# schematic.net
KiCad netlist of a schematic drawn in EAGLE
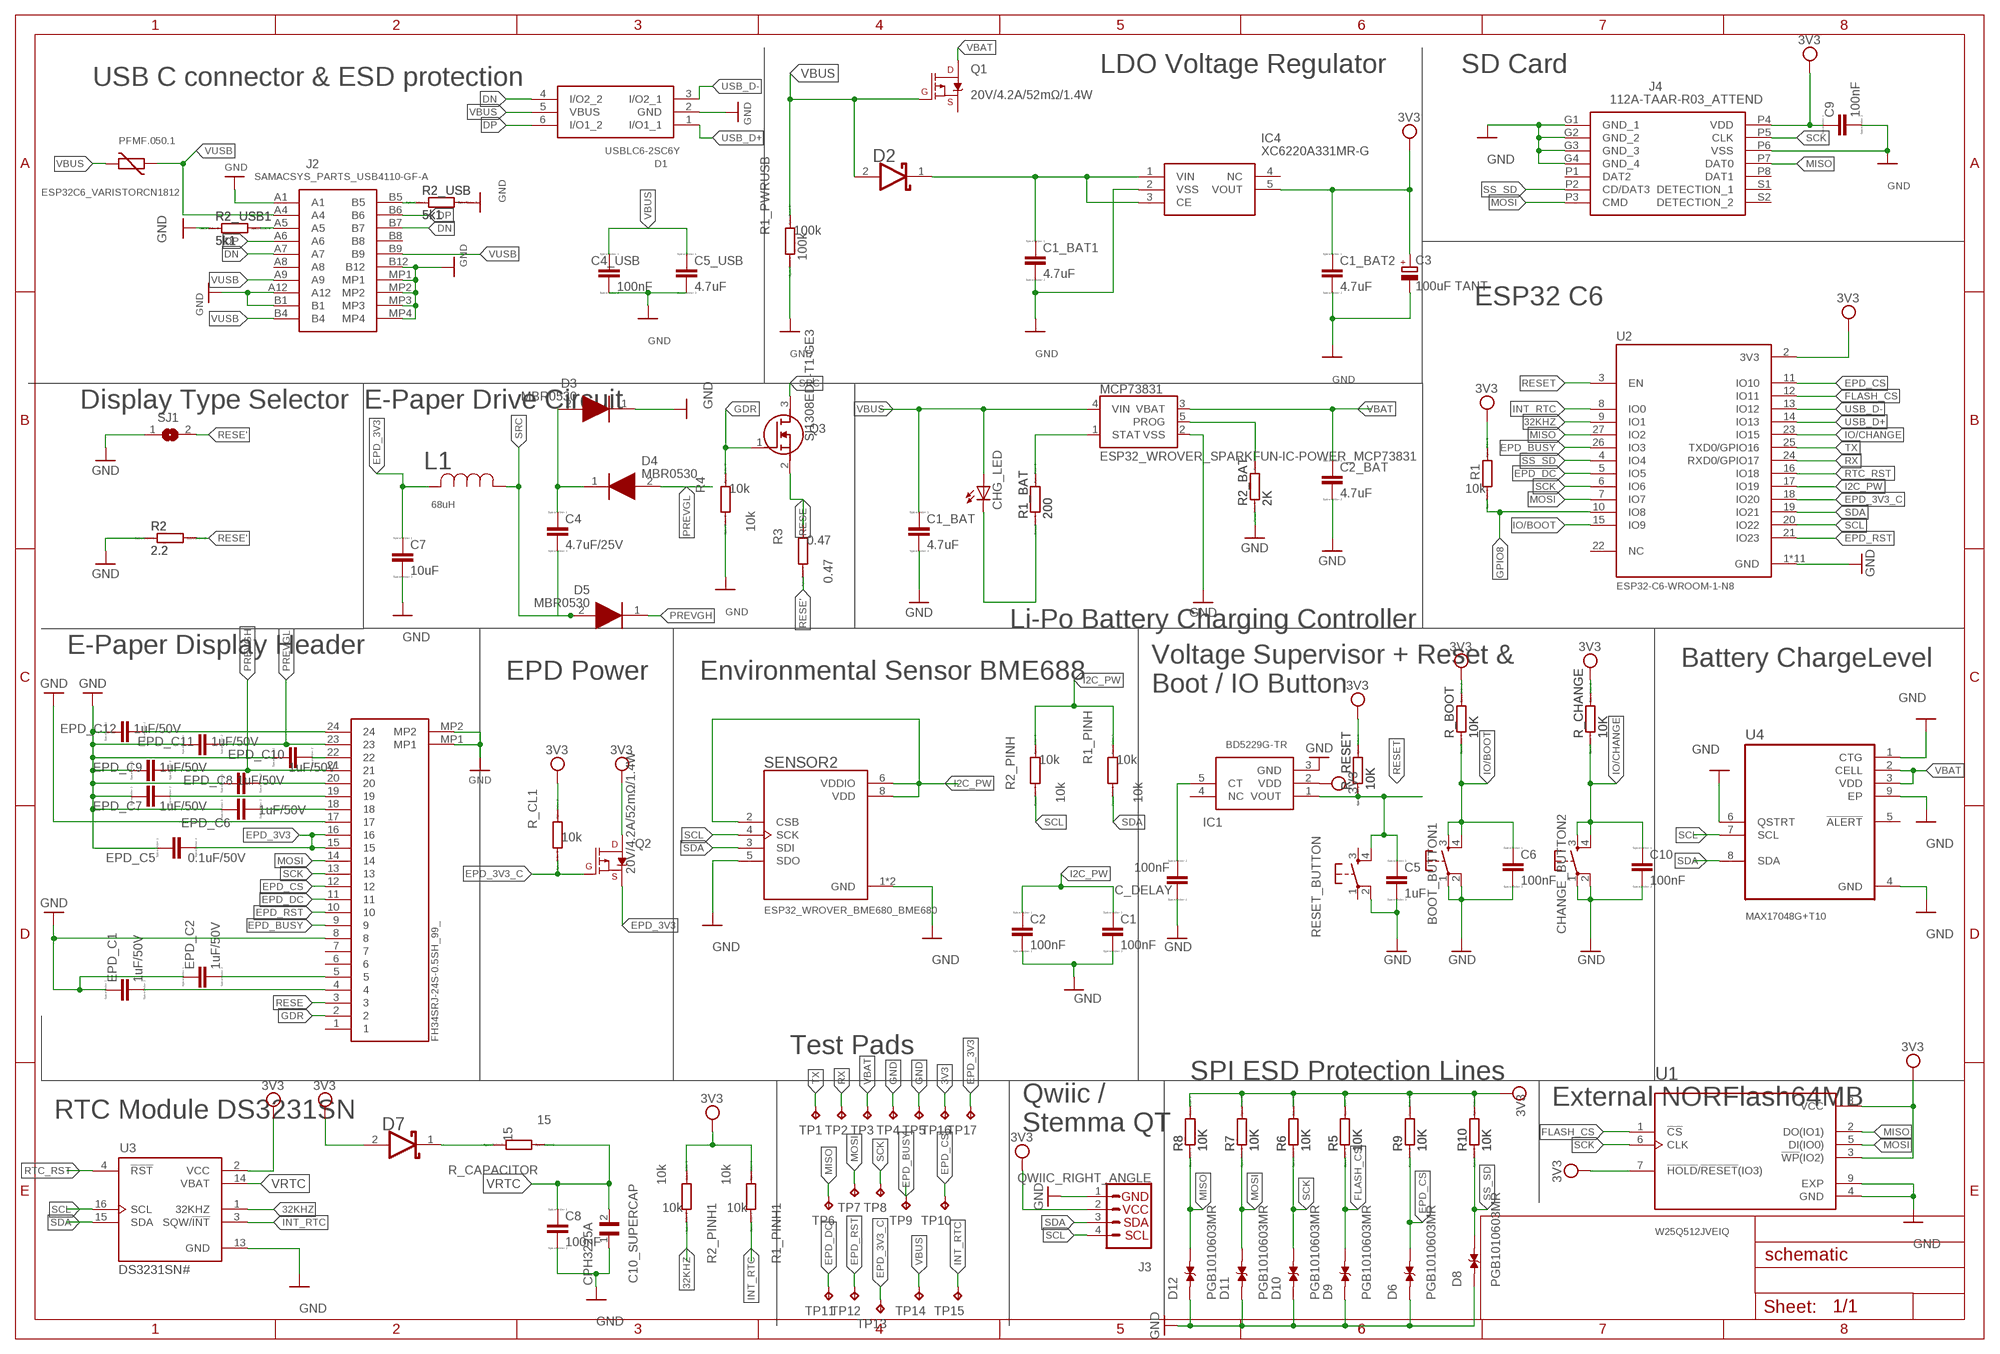
[diagram p0: schematic, sheet 1]

(export (version "E")
  (design (tool "Eeschema 10.0.6"))
  (components
    (comp (ref "BOOT_BUTTON1")
      (value "BUTTON_CUSYOMV1")
      (footprint "eagle-import:MYBUTTON")
      (libsource (lib "eagle-import") (part "BUTTON_CUSYOMV1"))
    )
    (comp (ref "C1")
      (value "100nF")
      (footprint "eagle-import:EAGLE-LTSPICE_C0402")
      (libsource (lib "eagle-import") (part "DeskAssistant v19 v1_vf.nBZE1evWTd-OCEZQXOw4Cw_EAGLE-LTSPICE_CC0402"))
    )
    (comp (ref "C1_BAT")
      (value "4.7uF")
      (footprint "eagle-import:EAGLE-LTSPICE_C0402")
      (libsource (lib "eagle-import") (part "EAGLE-LTSPICE_CC0402"))
    )
    (comp (ref "C1_BAT1")
      (value "4.7uF")
      (footprint "eagle-import:EAGLE-LTSPICE_C0402")
      (libsource (lib "eagle-import") (part "DeskAssistant v19 v1_vf.nBZE1evWTd-OCEZQXOw4Cw_EAGLE-LTSPICE_CC0402"))
    )
    (comp (ref "C1_BAT2")
      (value "4.7uF")
      (footprint "eagle-import:EAGLE-LTSPICE_C0402")
      (libsource (lib "eagle-import") (part "DeskAssistant v19 v1_vf.nBZE1evWTd-OCEZQXOw4Cw_EAGLE-LTSPICE_CC0402"))
    )
    (comp (ref "C2")
      (value "100nF")
      (footprint "eagle-import:EAGLE-LTSPICE_C0402")
      (libsource (lib "eagle-import") (part "DeskAssistant v19 v1_vf.nBZE1evWTd-OCEZQXOw4Cw_EAGLE-LTSPICE_CC0402"))
    )
    (comp (ref "C2_BAT")
      (value "4.7uF")
      (footprint "eagle-import:EAGLE-LTSPICE_C0402")
      (libsource (lib "eagle-import") (part "EAGLE-LTSPICE_CC0402"))
    )
    (comp (ref "C3")
      (value "100uF TANT")
      (footprint "eagle-import:RCL_CT3528")
      (libsource (lib "eagle-import") (part "RCL_CPOL-EUCT3528"))
    )
    (comp (ref "C4")
      (value "4.7uF/25V")
      (footprint "eagle-import:EAGLE-LTSPICE_C0402")
      (libsource (lib "eagle-import") (part "DeskAssistant v19 v1_vf.nBZE1evWTd-OCEZQXOw4Cw_EAGLE-LTSPICE_CC0402"))
    )
    (comp (ref "C4_USB")
      (value "100nF")
      (footprint "eagle-import:EAGLE-LTSPICE_C0402")
      (libsource (lib "eagle-import") (part "DeskAssistant v19 v1_vf.nBZE1evWTd-OCEZQXOw4Cw_EAGLE-LTSPICE_CC0402"))
    )
    (comp (ref "C5")
      (value "1uF")
      (footprint "eagle-import:EAGLE-LTSPICE_C0402")
      (libsource (lib "eagle-import") (part "EAGLE-LTSPICE_CC0402"))
    )
    (comp (ref "C5_USB")
      (value "4.7uF")
      (footprint "eagle-import:EAGLE-LTSPICE_C0402")
      (libsource (lib "eagle-import") (part "DeskAssistant v19 v1_vf.nBZE1evWTd-OCEZQXOw4Cw_EAGLE-LTSPICE_CC0402"))
    )
    (comp (ref "C6")
      (value "100nF")
      (footprint "eagle-import:EAGLE-LTSPICE_C0402")
      (libsource (lib "eagle-import") (part "EAGLE-LTSPICE_CC0402"))
    )
    (comp (ref "C7")
      (value "10uF")
      (footprint "eagle-import:EAGLE-LTSPICE_C0402")
      (libsource (lib "eagle-import") (part "DeskAssistant v19 v1_vf.nBZE1evWTd-OCEZQXOw4Cw_EAGLE-LTSPICE_CC0402"))
    )
    (comp (ref "C8")
      (value "100nF")
      (footprint "eagle-import:EAGLE-LTSPICE_C0402")
      (libsource (lib "eagle-import") (part "DeskAssistant v19 v1_vf.nBZE1evWTd-OCEZQXOw4Cw_EAGLE-LTSPICE_CC0402"))
    )
    (comp (ref "C9")
      (value "100nF")
      (footprint "eagle-import:EAGLE-LTSPICE_C0402")
      (libsource (lib "eagle-import") (part "DeskAssistant v19 v1_vf.nBZE1evWTd-OCEZQXOw4Cw_EAGLE-LTSPICE_CC0402"))
    )
    (comp (ref "C10")
      (value "100nF")
      (footprint "eagle-import:EAGLE-LTSPICE_C0402")
      (libsource (lib "eagle-import") (part "EAGLE-LTSPICE_CC0402"))
    )
    (comp (ref "C10_SUPERCAP")
      (value "CPH3225A")
      (footprint "eagle-import:CAPCP3225X100N")
      (fields (field (name "MF") "Seiko Instruments"))
      (libsource (lib "eagle-import") (part "CPH3225A"))
    )
    (comp (ref "CHANGE_BUTTON2")
      (value "BUTTON_CUSYOMV1")
      (footprint "eagle-import:MYBUTTON")
      (libsource (lib "eagle-import") (part "BUTTON_CUSYOMV1"))
    )
    (comp (ref "CHG_LED")
      (value "ADAFRUIT_LEDCHIP-LED0603")
      (footprint "eagle-import:ADAFRUIT_CHIP-LED0603")
      (libsource (lib "eagle-import") (part "ADAFRUIT_LEDCHIP-LED0603"))
    )
    (comp (ref "C_DELAY")
      (value "100nF")
      (footprint "eagle-import:EAGLE-LTSPICE_C0402")
      (libsource (lib "eagle-import") (part "EAGLE-LTSPICE_CC0402"))
    )
    (comp (ref "D1")
      (value "USBLC6-2SC6Y")
      (footprint "eagle-import:SOT95P280X145-6N")
      (fields (field (name "MF") "STMicroelectronics"))
      (libsource (lib "eagle-import") (part "USBLC6-2SC6Y"))
    )
    (comp (ref "D2")
      (value "ESP32_WROVER_AVX---SD0805S020S1R0_AVX_SD0805S020S1R0_0_0AVX_SD0805S020S1R0_0_0")
      (footprint "eagle-import:ESP32_WROVER_AVX---SD0805S020S1R0_AVX_SD0805S020S1R0_0")
      (fields
        (field (name "DIGIKEY_PART_NUMBER") "478-7800-1-ND")
        (field (name "MF") "AVX")
        (field (name "MOUSER_PART_NUMBER") "581-SD0805S020S1R0")
      )
      (libsource (lib "eagle-import") (part "ESP32_WROVER_AVX---SD0805S020S1R0_AVX_SD0805S020S1R0_0_0AVX_SD0805S020S1R0_0_0"))
    )
    (comp (ref "D3")
      (value "MBR0530")
      (footprint "eagle-import:SOD3716X135N")
      (fields (field (name "MF") "ON Semiconductor"))
      (libsource (lib "eagle-import") (part "MBR0530"))
    )
    (comp (ref "D4")
      (value "MBR0530")
      (footprint "eagle-import:SOD3716X135N")
      (fields (field (name "MF") "ON Semiconductor"))
      (libsource (lib "eagle-import") (part "MBR0530"))
    )
    (comp (ref "D5")
      (value "MBR0530")
      (footprint "eagle-import:SOD3716X135N")
      (fields (field (name "MF") "ON Semiconductor"))
      (libsource (lib "eagle-import") (part "MBR0530"))
    )
    (comp (ref "D6")
      (value "PGB1010603MR")
      (footprint "eagle-import:DIOC1608X36N")
      (fields (field (name "MF") "Littelfuse Inc."))
      (libsource (lib "eagle-import") (part "PGB1010603MR"))
    )
    (comp (ref "D7")
      (value "ESP32_WROVER_AVX---SD0805S020S1R0_AVX_SD0805S020S1R0_0_0AVX_SD0805S020S1R0_0_0")
      (footprint "eagle-import:ESP32_WROVER_AVX---SD0805S020S1R0_AVX_SD0805S020S1R0_0")
      (fields
        (field (name "DIGIKEY_PART_NUMBER") "478-7800-1-ND")
        (field (name "MF") "AVX")
        (field (name "MOUSER_PART_NUMBER") "581-SD0805S020S1R0")
      )
      (libsource (lib "eagle-import") (part "ESP32_WROVER_AVX---SD0805S020S1R0_AVX_SD0805S020S1R0_0_0AVX_SD0805S020S1R0_0_0"))
    )
    (comp (ref "D8")
      (value "PGB1010603MR")
      (footprint "eagle-import:DIOC1608X36N")
      (fields (field (name "MF") "Littelfuse Inc."))
      (libsource (lib "eagle-import") (part "PGB1010603MR"))
    )
    (comp (ref "D9")
      (value "PGB1010603MR")
      (footprint "eagle-import:DIOC1608X36N")
      (fields (field (name "MF") "Littelfuse Inc."))
      (libsource (lib "eagle-import") (part "PGB1010603MR"))
    )
    (comp (ref "D10")
      (value "PGB1010603MR")
      (footprint "eagle-import:DIOC1608X36N")
      (fields (field (name "MF") "Littelfuse Inc."))
      (libsource (lib "eagle-import") (part "PGB1010603MR"))
    )
    (comp (ref "D11")
      (value "PGB1010603MR")
      (footprint "eagle-import:DIOC1608X36N")
      (fields (field (name "MF") "Littelfuse Inc."))
      (libsource (lib "eagle-import") (part "PGB1010603MR"))
    )
    (comp (ref "D12")
      (value "PGB1010603MR")
      (footprint "eagle-import:DIOC1608X36N")
      (fields (field (name "MF") "Littelfuse Inc."))
      (libsource (lib "eagle-import") (part "PGB1010603MR"))
    )
    (comp (ref "EPD_C1")
      (value "1uF/50V")
      (footprint "eagle-import:EAGLE-LTSPICE_C0402")
      (libsource (lib "eagle-import") (part "EAGLE-LTSPICE_CC0402"))
    )
    (comp (ref "EPD_C2")
      (value "1uF/50V")
      (footprint "eagle-import:EAGLE-LTSPICE_C0402")
      (libsource (lib "eagle-import") (part "EAGLE-LTSPICE_CC0402"))
    )
    (comp (ref "EPD_C5")
      (value "0.1uF/50V")
      (footprint "eagle-import:EAGLE-LTSPICE_C0402")
      (libsource (lib "eagle-import") (part "EAGLE-LTSPICE_CC0402"))
    )
    (comp (ref "EPD_C6")
      (value "1uF/50V")
      (footprint "eagle-import:EAGLE-LTSPICE_C0402")
      (libsource (lib "eagle-import") (part "EAGLE-LTSPICE_CC0402"))
    )
    (comp (ref "EPD_C7")
      (value "1uF/50V")
      (footprint "eagle-import:EAGLE-LTSPICE_C0402")
      (libsource (lib "eagle-import") (part "EAGLE-LTSPICE_CC0402"))
    )
    (comp (ref "EPD_C8")
      (value "1uF/50V")
      (footprint "eagle-import:EAGLE-LTSPICE_C0402")
      (libsource (lib "eagle-import") (part "EAGLE-LTSPICE_CC0402"))
    )
    (comp (ref "EPD_C9")
      (value "1uF/50V")
      (footprint "eagle-import:EAGLE-LTSPICE_C0402")
      (libsource (lib "eagle-import") (part "EAGLE-LTSPICE_CC0402"))
    )
    (comp (ref "EPD_C10")
      (value "1uF/50V")
      (footprint "eagle-import:EAGLE-LTSPICE_C0402")
      (libsource (lib "eagle-import") (part "EAGLE-LTSPICE_CC0402"))
    )
    (comp (ref "EPD_C11")
      (value "1uF/50V")
      (footprint "eagle-import:EAGLE-LTSPICE_C0402")
      (libsource (lib "eagle-import") (part "EAGLE-LTSPICE_CC0402"))
    )
    (comp (ref "EPD_C12")
      (value "1uF/50V")
      (footprint "eagle-import:EAGLE-LTSPICE_C0402")
      (libsource (lib "eagle-import") (part "EAGLE-LTSPICE_CC0402"))
    )
    (comp (ref "FH34SRJ-24S-0.5SH_99_")
      (value "FH34SRJ-24S-0.5SH_99_")
      (footprint "eagle-import:FH34SRJ24S05SH99")
      (fields
        (field (name "MANUFACTURER_PART_NUMBER") "FH34SRJ-24S-0.5SH(99)")
        (field (name "MOUSER_PART_NUMBER") "798-FH34SRJ24S05SH99")
      )
      (libsource (lib "eagle-import") (part "FH34SRJ-24S-0.5SH_99_"))
    )
    (comp (ref "IC1")
      (value "BD5229G-TR")
      (footprint "eagle-import:SOT95P280X125-5N")
      (fields (field (name "MOUSER_PART_NUMBER") "755-BD5229G-TR"))
      (libsource (lib "eagle-import") (part "BD5229G-TR"))
    )
    (comp (ref "IC4")
      (value "XC6220A331MR-G")
      (footprint "eagle-import:SOT95P280X120-5N")
      (fields (field (name "MOUSER_PART_NUMBER") "865-XC6220A331MR-G"))
      (libsource (lib "eagle-import") (part "XC6220A331MR-G"))
    )
    (comp (ref "J2")
      (value "SAMACSYS_PARTS_USB4110-GF-A")
      (footprint "eagle-import:SAMACSYS_PARTS_USB4110GFA")
      (fields
        (field (name "MANUFACTURER_PART_NUMBER") "USB4110-GF-A")
        (field (name "MOUSER_PART_NUMBER") "640-USB4110-GF-A")
      )
      (libsource (lib "eagle-import") (part "SAMACSYS_PARTS_USB4110-GF-A"))
    )
    (comp (ref "J3")
      (value "QWIIC_RIGHT_ANGLE")
      (footprint "eagle-import:JST04_1MM_RA")
      (libsource (lib "eagle-import") (part "QWIIC_CONNECTORJS-1MM"))
    )
    (comp (ref "J4")
      (value "112A-TAAR-R03_ATTEND")
      (footprint "eagle-import:112ATAARR03ATTEND")
      (fields (field (name "MANUFACTURER_PART_NUMBER") "112A-TAAR-R03 ATTEND"))
      (libsource (lib "eagle-import") (part "112A-TAAR-R03_ATTEND"))
    )
    (comp (ref "L1")
      (value "68uH")
      (footprint "eagle-import:IND_4828-WE-TPC_WRE")
      (fields
        (field (name "MANUFACTURER_PART_NUMBER") "744043680")
        (field (name "COPYRIGHT") "Copyright (C) 2024 Ultra Librarian. All rights reserved.")
      )
      (libsource (lib "eagle-import") (part "744043680IND_4828-WE-TPC_WRE"))
    )
    (comp (ref "MCP73831")
      (value "ESP32_WROVER_SPARKFUN-IC-POWER_MCP73831")
      (footprint "eagle-import:ESP32_WROVER_SPARKFUN-IC-POWER_SOT23-5")
      (libsource (lib "eagle-import") (part "ESP32_WROVER_SPARKFUN-IC-POWER_MCP73831"))
    )
    (comp (ref "PFMF.050.1")
      (value "ESP32C6_VARISTORCN1812")
      (footprint "eagle-import:ESP32C6_VARISTOR_CT_CN1812")
      (libsource (lib "eagle-import") (part "ESP32C6_VARISTORCN1812"))
    )
    (comp (ref "Q1")
      (value "20V/4.2A/52mΩ/1.4W")
      (footprint "eagle-import:ESP32_WROVER_SPARKFUN-DISCRETESEMI_SOT23-3")
      (libsource (lib "eagle-import") (part "ESP32_WROVER_SPARKFUN-DISCRETESEMI_MOSFET_PCH-DMG2305UX-7"))
    )
    (comp (ref "Q2")
      (value "20V/4.2A/52mΩ/1.4W")
      (footprint "eagle-import:ESP32_WROVER_SPARKFUN-DISCRETESEMI_SOT23-3")
      (libsource (lib "eagle-import") (part "ESP32_WROVER_SPARKFUN-DISCRETESEMI_MOSFET_PCH-DMG2305UX-7"))
    )
    (comp (ref "Q3")
      (value "SI1308EDL-T1-GE3")
      (footprint "eagle-import:SOT65P210X110-3N")
      (fields (field (name "MF") "Vishay Siliconix"))
      (libsource (lib "eagle-import") (part "SI1308EDL-T1-GE3"))
    )
    (comp (ref "R1")
      (value "10k")
      (footprint "eagle-import:ESP32_WROVER_EAGLE-LTSPICE_R0402")
      (libsource (lib "eagle-import") (part "DeskAssistant v19 v1_vf.nBZE1evWTd-OCEZQXOw4Cw_ESP32_WROVER_EAGLE-LTSPICE_RR0402"))
    )
    (comp (ref "R1_BAT")
      (value "200")
      (footprint "eagle-import:ESP32_WROVER_EAGLE-LTSPICE_R0402")
      (libsource (lib "eagle-import") (part "ESP32_WROVER_EAGLE-LTSPICE_RR0402"))
    )
    (comp (ref "R1_PINH")
      (value "10k")
      (footprint "eagle-import:ESP32_WROVER_EAGLE-LTSPICE_R0402")
      (libsource (lib "eagle-import") (part "DeskAssistant v19 v1_vf.nBZE1evWTd-OCEZQXOw4Cw_ESP32_WROVER_EAGLE-LTSPICE_RR0402"))
    )
    (comp (ref "R1_PINH1")
      (value "10k")
      (footprint "eagle-import:ESP32_WROVER_EAGLE-LTSPICE_R0402")
      (libsource (lib "eagle-import") (part "DeskAssistant v19 v1_vf.nBZE1evWTd-OCEZQXOw4Cw_ESP32_WROVER_EAGLE-LTSPICE_RR0402"))
    )
    (comp (ref "R1_PWRUSB")
      (value "100k")
      (footprint "eagle-import:ESP32_WROVER_EAGLE-LTSPICE_R0402")
      (libsource (lib "eagle-import") (part "DeskAssistant v19 v1_vf.nBZE1evWTd-OCEZQXOw4Cw_ESP32_WROVER_EAGLE-LTSPICE_RR0402"))
    )
    (comp (ref "R2")
      (value "2.2")
      (footprint "eagle-import:ESP32_WROVER_EAGLE-LTSPICE_R0402")
      (libsource (lib "eagle-import") (part "ESP32_WROVER_EAGLE-LTSPICE_RR0402"))
    )
    (comp (ref "R2_BAT")
      (value "2K")
      (footprint "eagle-import:ESP32_WROVER_EAGLE-LTSPICE_R0402")
      (libsource (lib "eagle-import") (part "ESP32_WROVER_EAGLE-LTSPICE_RR0402"))
    )
    (comp (ref "R2_PINH")
      (value "10k")
      (footprint "eagle-import:ESP32_WROVER_EAGLE-LTSPICE_R0402")
      (libsource (lib "eagle-import") (part "DeskAssistant v19 v1_vf.nBZE1evWTd-OCEZQXOw4Cw_ESP32_WROVER_EAGLE-LTSPICE_RR0402"))
    )
    (comp (ref "R2_PINH1")
      (value "10k")
      (footprint "eagle-import:ESP32_WROVER_EAGLE-LTSPICE_R0402")
      (libsource (lib "eagle-import") (part "DeskAssistant v19 v1_vf.nBZE1evWTd-OCEZQXOw4Cw_ESP32_WROVER_EAGLE-LTSPICE_RR0402"))
    )
    (comp (ref "R2_USB")
      (value "5k1")
      (footprint "eagle-import:ESP32_WROVER_EAGLE-LTSPICE_R0402")
      (libsource (lib "eagle-import") (part "DeskAssistant v19 v1_vf.nBZE1evWTd-OCEZQXOw4Cw_ESP32_WROVER_EAGLE-LTSPICE_RR0402"))
    )
    (comp (ref "R2_USB1")
      (value "5k1")
      (footprint "eagle-import:ESP32_WROVER_EAGLE-LTSPICE_R0402")
      (libsource (lib "eagle-import") (part "DeskAssistant v19 v1_vf.nBZE1evWTd-OCEZQXOw4Cw_ESP32_WROVER_EAGLE-LTSPICE_RR0402"))
    )
    (comp (ref "R3")
      (value "0.47")
      (footprint "eagle-import:ESP32_WROVER_EAGLE-LTSPICE_R0402")
      (libsource (lib "eagle-import") (part "DeskAssistant v19 v1_vf.nBZE1evWTd-OCEZQXOw4Cw_ESP32_WROVER_EAGLE-LTSPICE_RR0402"))
    )
    (comp (ref "R4")
      (value "10k")
      (footprint "eagle-import:ESP32_WROVER_EAGLE-LTSPICE_R0402")
      (libsource (lib "eagle-import") (part "DeskAssistant v19 v1_vf.nBZE1evWTd-OCEZQXOw4Cw_ESP32_WROVER_EAGLE-LTSPICE_RR0402"))
    )
    (comp (ref "R5")
      (value "10K")
      (footprint "eagle-import:ESP32_WROVER_EAGLE-LTSPICE_R0402")
      (libsource (lib "eagle-import") (part "ESP32_WROVER_EAGLE-LTSPICE_RR0402"))
    )
    (comp (ref "R6")
      (value "10K")
      (footprint "eagle-import:ESP32_WROVER_EAGLE-LTSPICE_R0402")
      (libsource (lib "eagle-import") (part "ESP32_WROVER_EAGLE-LTSPICE_RR0402"))
    )
    (comp (ref "R7")
      (value "10K")
      (footprint "eagle-import:ESP32_WROVER_EAGLE-LTSPICE_R0402")
      (libsource (lib "eagle-import") (part "ESP32_WROVER_EAGLE-LTSPICE_RR0402"))
    )
    (comp (ref "R8")
      (value "10K")
      (footprint "eagle-import:ESP32_WROVER_EAGLE-LTSPICE_R0402")
      (libsource (lib "eagle-import") (part "ESP32_WROVER_EAGLE-LTSPICE_RR0402"))
    )
    (comp (ref "R9")
      (value "10K")
      (footprint "eagle-import:ESP32_WROVER_EAGLE-LTSPICE_R0402")
      (libsource (lib "eagle-import") (part "ESP32_WROVER_EAGLE-LTSPICE_RR0402"))
    )
    (comp (ref "R10")
      (value "10K")
      (footprint "eagle-import:ESP32_WROVER_EAGLE-LTSPICE_R0402")
      (libsource (lib "eagle-import") (part "ESP32_WROVER_EAGLE-LTSPICE_RR0402"))
    )
    (comp (ref "RESET_BUTTON")
      (value "BUTTON_CUSYOMV1")
      (footprint "eagle-import:MYBUTTON")
      (libsource (lib "eagle-import") (part "BUTTON_CUSYOMV1"))
    )
    (comp (ref "R_BOOT")
      (value "10K")
      (footprint "eagle-import:ESP32_WROVER_EAGLE-LTSPICE_R0402")
      (libsource (lib "eagle-import") (part "ESP32_WROVER_EAGLE-LTSPICE_RR0402"))
    )
    (comp (ref "R_CAPACITOR")
      (value "15")
      (footprint "eagle-import:ESP32_WROVER_EAGLE-LTSPICE_R0402")
      (libsource (lib "eagle-import") (part "DeskAssistant v19 v1_vf.nBZE1evWTd-OCEZQXOw4Cw_ESP32_WROVER_EAGLE-LTSPICE_RR0402"))
    )
    (comp (ref "R_CHANGE")
      (value "10K")
      (footprint "eagle-import:ESP32_WROVER_EAGLE-LTSPICE_R0402")
      (libsource (lib "eagle-import") (part "ESP32_WROVER_EAGLE-LTSPICE_RR0402"))
    )
    (comp (ref "R_CL1")
      (value "10k")
      (footprint "eagle-import:ESP32_WROVER_EAGLE-LTSPICE_R0402")
      (libsource (lib "eagle-import") (part "DeskAssistant v19 v1_vf.nBZE1evWTd-OCEZQXOw4Cw_ESP32_WROVER_EAGLE-LTSPICE_RR0402"))
    )
    (comp (ref "R_RESET")
      (value "10K")
      (footprint "eagle-import:ESP32_WROVER_EAGLE-LTSPICE_R0402")
      (libsource (lib "eagle-import") (part "ESP32_WROVER_EAGLE-LTSPICE_RR0402"))
    )
    (comp (ref "SENSOR2")
      (value "ESP32_WROVER_BME680_BME680")
      (footprint "eagle-import:ESP32_WROVER_BME680_PSON80P300X300X100-8N")
      (fields (field (name "MF") "Bosch Sensortec") (field (name "MP") "BME680"))
      (libsource (lib "eagle-import") (part "ESP32_WROVER_BME680_BME680"))
    )
    (comp (ref "SJ1") (value "SJ") (footprint "eagle-import:SJ") (libsource (lib "eagle-import") (part "SJ")))
    (comp (ref "TP1")
      (value "TPTP20R")
      (footprint "eagle-import:TP20R")
      (libsource (lib "eagle-import") (part "TPTP20R"))
    )
    (comp (ref "TP2")
      (value "TPTP20R")
      (footprint "eagle-import:TP20R")
      (libsource (lib "eagle-import") (part "TPTP20R"))
    )
    (comp (ref "TP3")
      (value "TPTP20R")
      (footprint "eagle-import:TP20R")
      (libsource (lib "eagle-import") (part "TPTP20R"))
    )
    (comp (ref "TP4")
      (value "TPTP20R")
      (footprint "eagle-import:TP20R")
      (libsource (lib "eagle-import") (part "TPTP20R"))
    )
    (comp (ref "TP5")
      (value "TPTP20R")
      (footprint "eagle-import:TP20R")
      (libsource (lib "eagle-import") (part "TPTP20R"))
    )
    (comp (ref "TP6")
      (value "TPTP20R")
      (footprint "eagle-import:TP20R")
      (libsource (lib "eagle-import") (part "TPTP20R"))
    )
    (comp (ref "TP7")
      (value "TPTP20R")
      (footprint "eagle-import:TP20R")
      (libsource (lib "eagle-import") (part "TPTP20R"))
    )
    (comp (ref "TP8")
      (value "TPTP20R")
      (footprint "eagle-import:TP20R")
      (libsource (lib "eagle-import") (part "TPTP20R"))
    )
    (comp (ref "TP9")
      (value "TPTP20R")
      (footprint "eagle-import:TP20R")
      (libsource (lib "eagle-import") (part "TPTP20R"))
    )
    (comp (ref "TP10")
      (value "TPTP20R")
      (footprint "eagle-import:TP20R")
      (libsource (lib "eagle-import") (part "TPTP20R"))
    )
    (comp (ref "TP11")
      (value "TPTP20R")
      (footprint "eagle-import:TP20R")
      (libsource (lib "eagle-import") (part "TPTP20R"))
    )
    (comp (ref "TP12")
      (value "TPTP20R")
      (footprint "eagle-import:TP20R")
      (libsource (lib "eagle-import") (part "TPTP20R"))
    )
    (comp (ref "TP13")
      (value "TPTP20R")
      (footprint "eagle-import:TP20R")
      (libsource (lib "eagle-import") (part "TPTP20R"))
    )
    (comp (ref "TP14")
      (value "TPTP20R")
      (footprint "eagle-import:TP20R")
      (libsource (lib "eagle-import") (part "TPTP20R"))
    )
    (comp (ref "TP15")
      (value "TPTP20R")
      (footprint "eagle-import:TP20R")
      (libsource (lib "eagle-import") (part "TPTP20R"))
    )
    (comp (ref "TP16")
      (value "TPTP20R")
      (footprint "eagle-import:TP20R")
      (libsource (lib "eagle-import") (part "TPTP20R"))
    )
    (comp (ref "TP17")
      (value "TPTP20R")
      (footprint "eagle-import:TP20R")
      (libsource (lib "eagle-import") (part "TPTP20R"))
    )
    (comp (ref "U1")
      (value "W25Q512JVEIQ")
      (footprint "eagle-import:SON127P600X800X80-9N")
      (fields (field (name "MF") "Winbond Electronics"))
      (libsource (lib "eagle-import") (part "W25Q512JVEIQ"))
    )
    (comp (ref "U2")
      (value "ESP32-C6-WROOM-1-N8")
      (footprint "eagle-import:XCVR_ESP32-C6-WROOM-1-N8")
      (fields (field (name "MF") "Espressif Systems"))
      (libsource (lib "eagle-import") (part "ESP32-C6-WROOM-1-N8"))
    )
    (comp (ref "U3")
      (value "DS3231SN#")
      (footprint "eagle-import:SOIC127P1032X265-16N")
      (fields (field (name "MF") "Analog Devices"))
      (libsource (lib "eagle-import") (part "DS3231SN#"))
    )
    (comp (ref "U4")
      (value "MAX17048G+T10")
      (footprint "eagle-import:SON50P200X200X80-9N")
      (fields (field (name "MF") "Analog Devices"))
      (libsource (lib "eagle-import") (part "MAX17048G+T10"))
    )
  )
  (nets
    (net (code "1") (name "3V3") (class "Default")
      (node (ref "C1_BAT2") (pin "1") (pinfunction "1_1") (pintype "passive"))
      (node (ref "C3") (pin "+") (pinfunction "+_+") (pintype "passive"))
      (node (ref "C9") (pin "1") (pinfunction "1_1") (pintype "passive"))
      (node (ref "D7") (pin "2") (pinfunction "ANODE_2") (pintype "bidirectional"))
      (node (ref "IC1") (pin "2") (pinfunction "VDD_2") (pintype "bidirectional"))
      (node (ref "IC4") (pin "5") (pinfunction "VOUT_5") (pintype "bidirectional"))
      (node (ref "J3") (pin "2") (pinfunction "2_2") (pintype "power_in"))
      (node (ref "J4") (pin "P4") (pinfunction "VDD_P4") (pintype "bidirectional"))
      (node (ref "Q2") (pin "3") (pinfunction "D_3") (pintype "bidirectional"))
      (node (ref "R1") (pin "2") (pinfunction "2_2") (pintype "passive"))
      (node (ref "R10") (pin "2") (pinfunction "2_2") (pintype "passive"))
      (node (ref "R1_PINH1") (pin "1") (pinfunction "1_1") (pintype "passive"))
      (node (ref "R2_PINH1") (pin "1") (pinfunction "1_1") (pintype "passive"))
      (node (ref "R5") (pin "2") (pinfunction "2_2") (pintype "passive"))
      (node (ref "R6") (pin "2") (pinfunction "2_2") (pintype "passive"))
      (node (ref "R7") (pin "2") (pinfunction "2_2") (pintype "passive"))
      (node (ref "R8") (pin "2") (pinfunction "2_2") (pintype "passive"))
      (node (ref "R9") (pin "2") (pinfunction "2_2") (pintype "passive"))
      (node (ref "R_BOOT") (pin "2") (pinfunction "2_2") (pintype "passive"))
      (node (ref "R_CHANGE") (pin "2") (pinfunction "2_2") (pintype "passive"))
      (node (ref "R_CL1") (pin "2") (pinfunction "2_2") (pintype "passive"))
      (node (ref "R_RESET") (pin "2") (pinfunction "2_2") (pintype "passive"))
      (node (ref "TP16") (pin "TP") (pinfunction "TP_TP") (pintype "input"))
      (node (ref "U1") (pin "3") (pinfunction "~{WP}(IO2)_3") (pintype "bidirectional"))
      (node (ref "U1") (pin "7") (pinfunction "~{HOLD}/~{RESET}(IO3)_7") (pintype "bidirectional"))
      (node (ref "U1") (pin "8") (pinfunction "VCC_8") (pintype "power_in"))
      (node (ref "U2") (pin "2") (pinfunction "3V3_2") (pintype "power_in"))
      (node (ref "U3") (pin "2") (pinfunction "VCC_2") (pintype "power_in"))
    )
    (net (code "2") (name "32KHZ") (class "Default")
      (node (ref "R2_PINH1") (pin "2") (pinfunction "2_2") (pintype "passive"))
      (node (ref "U2") (pin "9") (pinfunction "IO1_9") (pintype "bidirectional"))
      (node (ref "U3") (pin "1") (pinfunction "32KHZ_1") (pintype "output"))
    )
    (net (code "3") (name "DN") (class "Default")
      (node (ref "D1") (pin "4") (pinfunction "I/O2_2_4") (pintype "bidirectional"))
      (node (ref "J2") (pin "A7") (pinfunction "A7_A7") (pintype "bidirectional"))
      (node (ref "J2") (pin "B7") (pinfunction "B7_B7") (pintype "bidirectional"))
    )
    (net (code "4") (name "DP") (class "Default")
      (node (ref "D1") (pin "6") (pinfunction "I/O1_2_6") (pintype "bidirectional"))
      (node (ref "J2") (pin "A6") (pinfunction "A6_A6") (pintype "bidirectional"))
      (node (ref "J2") (pin "B6") (pinfunction "B6_B6") (pintype "bidirectional"))
    )
    (net (code "5") (name "EPD_3V3") (class "Default")
      (node (ref "C7") (pin "1") (pinfunction "1_1") (pintype "passive"))
      (node (ref "EPD_C5") (pin "2") (pinfunction "2_2") (pintype "passive"))
      (node (ref "FH34SRJ-24S-0.5SH_99_") (pin "15") (pinfunction "15_15") (pintype "bidirectional"))
      (node (ref "FH34SRJ-24S-0.5SH_99_") (pin "16") (pinfunction "16_16") (pintype "bidirectional"))
      (node (ref "L1") (pin "2") (pinfunction "2_2") (pintype "passive"))
      (node (ref "Q2") (pin "2") (pinfunction "S_2") (pintype "bidirectional"))
      (node (ref "TP17") (pin "TP") (pinfunction "TP_TP") (pintype "input"))
    )
    (net (code "6") (name "EPD_3V3_C") (class "Default")
      (node (ref "Q2") (pin "1") (pinfunction "G_1") (pintype "bidirectional"))
      (node (ref "R_CL1") (pin "1") (pinfunction "1_1") (pintype "passive"))
      (node (ref "TP13") (pin "TP") (pinfunction "TP_TP") (pintype "input"))
      (node (ref "U2") (pin "18") (pinfunction "IO20_18") (pintype "bidirectional"))
    )
    (net (code "7") (name "EPD_BUSY") (class "Default")
      (node (ref "FH34SRJ-24S-0.5SH_99_") (pin "9") (pinfunction "9_9") (pintype "bidirectional"))
      (node (ref "TP9") (pin "TP") (pinfunction "TP_TP") (pintype "input"))
      (node (ref "U2") (pin "26") (pinfunction "IO3_26") (pintype "bidirectional"))
    )
    (net (code "8") (name "EPD_CS") (class "Default")
      (node (ref "D6") (pin "2") (pinfunction "2_2") (pintype "passive"))
      (node (ref "FH34SRJ-24S-0.5SH_99_") (pin "12") (pinfunction "12_12") (pintype "bidirectional"))
      (node (ref "R9") (pin "1") (pinfunction "1_1") (pintype "passive"))
      (node (ref "TP10") (pin "TP") (pinfunction "TP_TP") (pintype "input"))
      (node (ref "U2") (pin "11") (pinfunction "IO10_11") (pintype "bidirectional"))
    )
    (net (code "9") (name "EPD_DC") (class "Default")
      (node (ref "FH34SRJ-24S-0.5SH_99_") (pin "11") (pinfunction "11_11") (pintype "bidirectional"))
      (node (ref "TP11") (pin "TP") (pinfunction "TP_TP") (pintype "input"))
      (node (ref "U2") (pin "5") (pinfunction "IO5_5") (pintype "bidirectional"))
    )
    (net (code "10") (name "EPD_RST") (class "Default")
      (node (ref "FH34SRJ-24S-0.5SH_99_") (pin "10") (pinfunction "10_10") (pintype "bidirectional"))
      (node (ref "TP12") (pin "TP") (pinfunction "TP_TP") (pintype "input"))
      (node (ref "U2") (pin "21") (pinfunction "IO23_21") (pintype "bidirectional"))
    )
    (net (code "11") (name "FLASH_CS") (class "Default")
      (node (ref "D9") (pin "2") (pinfunction "2_2") (pintype "passive"))
      (node (ref "R5") (pin "1") (pinfunction "1_1") (pintype "passive"))
      (node (ref "U1") (pin "1") (pinfunction "~{CS}_1") (pintype "input"))
      (node (ref "U2") (pin "12") (pinfunction "IO11_12") (pintype "bidirectional"))
    )
    (net (code "12") (name "GDR") (class "Default")
      (node (ref "FH34SRJ-24S-0.5SH_99_") (pin "2") (pinfunction "2_2") (pintype "bidirectional"))
      (node (ref "Q3") (pin "1") (pinfunction "G_1") (pintype "bidirectional"))
      (node (ref "R4") (pin "2") (pinfunction "2_2") (pintype "passive"))
    )
    (net (code "13") (name "GND") (class "Default")
      (node (ref "BOOT_BUTTON1") (pin "1") (pinfunction "1_1") (pintype "passive"))
      (node (ref "BOOT_BUTTON1") (pin "2") (pinfunction "2_2") (pintype "passive"))
      (node (ref "C1") (pin "2") (pinfunction "2_2") (pintype "passive"))
      (node (ref "C10") (pin "2") (pinfunction "2_2") (pintype "passive"))
      (node (ref "C10_SUPERCAP") (pin "1") (pinfunction "1_1") (pintype "passive"))
      (node (ref "C1_BAT") (pin "2") (pinfunction "2_2") (pintype "passive"))
      (node (ref "C1_BAT1") (pin "2") (pinfunction "2_2") (pintype "passive"))
      (node (ref "C1_BAT2") (pin "2") (pinfunction "2_2") (pintype "passive"))
      (node (ref "C2") (pin "2") (pinfunction "2_2") (pintype "passive"))
      (node (ref "C2_BAT") (pin "2") (pinfunction "2_2") (pintype "passive"))
      (node (ref "C3") (pin "-") (pinfunction "-_-") (pintype "passive"))
      (node (ref "C4_USB") (pin "2") (pinfunction "2_2") (pintype "passive"))
      (node (ref "C5") (pin "2") (pinfunction "2_2") (pintype "passive"))
      (node (ref "C5_USB") (pin "2") (pinfunction "2_2") (pintype "passive"))
      (node (ref "C6") (pin "2") (pinfunction "2_2") (pintype "passive"))
      (node (ref "C7") (pin "2") (pinfunction "2_2") (pintype "passive"))
      (node (ref "C8") (pin "2") (pinfunction "2_2") (pintype "passive"))
      (node (ref "C9") (pin "2") (pinfunction "2_2") (pintype "passive"))
      (node (ref "CHANGE_BUTTON2") (pin "1") (pinfunction "1_1") (pintype "passive"))
      (node (ref "CHANGE_BUTTON2") (pin "2") (pinfunction "2_2") (pintype "passive"))
      (node (ref "C_DELAY") (pin "1") (pinfunction "1_1") (pintype "passive"))
      (node (ref "D1") (pin "2") (pinfunction "GND_2") (pintype "bidirectional"))
      (node (ref "D10") (pin "1") (pinfunction "1_1") (pintype "passive"))
      (node (ref "D11") (pin "1") (pinfunction "1_1") (pintype "passive"))
      (node (ref "D12") (pin "1") (pinfunction "1_1") (pintype "passive"))
      (node (ref "D3") (pin "1") (pinfunction "K_1") (pintype "bidirectional"))
      (node (ref "D6") (pin "1") (pinfunction "1_1") (pintype "passive"))
      (node (ref "D8") (pin "1") (pinfunction "1_1") (pintype "passive"))
      (node (ref "D9") (pin "1") (pinfunction "1_1") (pintype "passive"))
      (node (ref "EPD_C1") (pin "1") (pinfunction "1_1") (pintype "passive"))
      (node (ref "EPD_C10") (pin "1") (pinfunction "1_1") (pintype "passive"))
      (node (ref "EPD_C11") (pin "1") (pinfunction "1_1") (pintype "passive"))
      (node (ref "EPD_C12") (pin "1") (pinfunction "1_1") (pintype "passive"))
      (node (ref "EPD_C2") (pin "1") (pinfunction "1_1") (pintype "passive"))
      (node (ref "EPD_C5") (pin "1") (pinfunction "1_1") (pintype "passive"))
      (node (ref "EPD_C6") (pin "1") (pinfunction "1_1") (pintype "passive"))
      (node (ref "EPD_C7") (pin "1") (pinfunction "1_1") (pintype "passive"))
      (node (ref "EPD_C8") (pin "1") (pinfunction "1_1") (pintype "passive"))
      (node (ref "EPD_C9") (pin "1") (pinfunction "1_1") (pintype "passive"))
      (node (ref "FH34SRJ-24S-0.5SH_99_") (pin "17") (pinfunction "17_17") (pintype "bidirectional"))
      (node (ref "FH34SRJ-24S-0.5SH_99_") (pin "8") (pinfunction "8_8") (pintype "bidirectional"))
      (node (ref "FH34SRJ-24S-0.5SH_99_") (pin "MP1") (pinfunction "MP1_MP1") (pintype "bidirectional"))
      (node (ref "FH34SRJ-24S-0.5SH_99_") (pin "MP2") (pinfunction "MP2_MP2") (pintype "bidirectional"))
      (node (ref "IC1") (pin "3") (pinfunction "GND_3") (pintype "bidirectional"))
      (node (ref "IC4") (pin "2") (pinfunction "VSS_2") (pintype "bidirectional"))
      (node (ref "J2") (pin "A1") (pinfunction "A1_A1") (pintype "bidirectional"))
      (node (ref "J2") (pin "A12") (pinfunction "A12_A12") (pintype "bidirectional"))
      (node (ref "J2") (pin "B1") (pinfunction "B1_B1") (pintype "bidirectional"))
      (node (ref "J2") (pin "B12") (pinfunction "B12_B12") (pintype "bidirectional"))
      (node (ref "J2") (pin "MP1") (pinfunction "MP1_MP1") (pintype "bidirectional"))
      (node (ref "J2") (pin "MP2") (pinfunction "MP2_MP2") (pintype "bidirectional"))
      (node (ref "J2") (pin "MP3") (pinfunction "MP3_MP3") (pintype "bidirectional"))
      (node (ref "J2") (pin "MP4") (pinfunction "MP4_MP4") (pintype "bidirectional"))
      (node (ref "J3") (pin "1") (pinfunction "1_1") (pintype "power_in"))
      (node (ref "J4") (pin "G1") (pinfunction "GND_1_G1") (pintype "bidirectional"))
      (node (ref "J4") (pin "G2") (pinfunction "GND_2_G2") (pintype "bidirectional"))
      (node (ref "J4") (pin "G3") (pinfunction "GND_3_G3") (pintype "bidirectional"))
      (node (ref "J4") (pin "G4") (pinfunction "GND_4_G4") (pintype "bidirectional"))
      (node (ref "J4") (pin "P6") (pinfunction "VSS_P6") (pintype "bidirectional"))
      (node (ref "MCP73831") (pin "2") (pinfunction "VSS_2") (pintype "power_in"))
      (node (ref "R1_PWRUSB") (pin "1") (pinfunction "1_1") (pintype "passive"))
      (node (ref "R2") (pin "1") (pinfunction "1_1") (pintype "passive"))
      (node (ref "R2_BAT") (pin "1") (pinfunction "1_1") (pintype "passive"))
      (node (ref "R2_USB") (pin "2") (pinfunction "2_2") (pintype "passive"))
      (node (ref "R2_USB1") (pin "1") (pinfunction "1_1") (pintype "passive"))
      (node (ref "R4") (pin "1") (pinfunction "1_1") (pintype "passive"))
      (node (ref "RESET_BUTTON") (pin "2") (pinfunction "2_2") (pintype "passive"))
      (node (ref "SENSOR2") (pin "1") (pinfunction "GND_1") (pintype "power_in"))
      (node (ref "SENSOR2") (pin "5") (pinfunction "SDO_5") (pintype "bidirectional"))
      (node (ref "SENSOR2") (pin "7") (pinfunction "GND_7") (pintype "power_in"))
      (node (ref "SJ1") (pin "1") (pinfunction "1_1") (pintype "passive"))
      (node (ref "TP4") (pin "TP") (pinfunction "TP_TP") (pintype "input"))
      (node (ref "TP5") (pin "TP") (pinfunction "TP_TP") (pintype "input"))
      (node (ref "U1") (pin "4") (pinfunction "GND_4") (pintype "power_in"))
      (node (ref "U1") (pin "9") (pinfunction "EXP_9") (pintype "passive"))
      (node (ref "U2") (pin "1") (pinfunction "GND_1") (pintype "power_in"))
      (node (ref "U2") (pin "28") (pinfunction "GND_28") (pintype "power_in"))
      (node (ref "U2") (pin "29_1") (pinfunction "GND_29_1") (pintype "power_in"))
      (node (ref "U2") (pin "29_2") (pinfunction "GND_29_2") (pintype "power_in"))
      (node (ref "U2") (pin "29_3") (pinfunction "GND_29_3") (pintype "power_in"))
      (node (ref "U2") (pin "29_4") (pinfunction "GND_29_4") (pintype "power_in"))
      (node (ref "U2") (pin "29_5") (pinfunction "GND_29_5") (pintype "power_in"))
      (node (ref "U2") (pin "29_6") (pinfunction "GND_29_6") (pintype "power_in"))
      (node (ref "U2") (pin "29_7") (pinfunction "GND_29_7") (pintype "power_in"))
      (node (ref "U2") (pin "29_8") (pinfunction "GND_29_8") (pintype "power_in"))
      (node (ref "U2") (pin "29_9") (pinfunction "GND_29_9") (pintype "power_in"))
      (node (ref "U3") (pin "13") (pinfunction "GND_13") (pintype "power_in"))
      (node (ref "U4") (pin "1") (pinfunction "CTG_1") (pintype "power_in"))
      (node (ref "U4") (pin "4") (pinfunction "GND_4") (pintype "power_in"))
      (node (ref "U4") (pin "6") (pinfunction "QSTRT_6") (pintype "input"))
      (node (ref "U4") (pin "9") (pinfunction "EP_9") (pintype "power_in"))
    )
    (net (code "14") (name "GPIO8") (class "Default")
      (node (ref "R1") (pin "1") (pinfunction "1_1") (pintype "passive"))
      (node (ref "U2") (pin "10") (pinfunction "IO8_10") (pintype "bidirectional"))
    )
    (net (code "15") (name "I2C_PW") (class "Default")
      (node (ref "C1") (pin "1") (pinfunction "1_1") (pintype "passive"))
      (node (ref "C2") (pin "1") (pinfunction "1_1") (pintype "passive"))
      (node (ref "R1_PINH") (pin "2") (pinfunction "2_2") (pintype "passive"))
      (node (ref "R2_PINH") (pin "2") (pinfunction "2_2") (pintype "passive"))
      (node (ref "SENSOR2") (pin "2") (pinfunction "CSB_2") (pintype "input"))
      (node (ref "SENSOR2") (pin "6") (pinfunction "VDDIO_6") (pintype "power_in"))
      (node (ref "SENSOR2") (pin "8") (pinfunction "VDD_8") (pintype "power_in"))
      (node (ref "U2") (pin "17") (pinfunction "IO19_17") (pintype "bidirectional"))
    )
    (net (code "16") (name "INT_RTC") (class "Default")
      (node (ref "R1_PINH1") (pin "2") (pinfunction "2_2") (pintype "passive"))
      (node (ref "TP15") (pin "TP") (pinfunction "TP_TP") (pintype "input"))
      (node (ref "U2") (pin "8") (pinfunction "IO0_8") (pintype "bidirectional"))
      (node (ref "U3") (pin "3") (pinfunction "SQW/~{INT}_3") (pintype "output"))
    )
    (net (code "17") (name "IO{slash}BOOT") (class "Default")
      (node (ref "BOOT_BUTTON1") (pin "3") (pinfunction "3_3") (pintype "passive"))
      (node (ref "BOOT_BUTTON1") (pin "4") (pinfunction "4_4") (pintype "passive"))
      (node (ref "C6") (pin "1") (pinfunction "1_1") (pintype "passive"))
      (node (ref "R_BOOT") (pin "1") (pinfunction "1_1") (pintype "passive"))
      (node (ref "U2") (pin "15") (pinfunction "IO9_15") (pintype "bidirectional"))
    )
    (net (code "18") (name "IO{slash}CHANGE") (class "Default")
      (node (ref "C10") (pin "1") (pinfunction "1_1") (pintype "passive"))
      (node (ref "CHANGE_BUTTON2") (pin "3") (pinfunction "3_3") (pintype "passive"))
      (node (ref "CHANGE_BUTTON2") (pin "4") (pinfunction "4_4") (pintype "passive"))
      (node (ref "R_CHANGE") (pin "1") (pinfunction "1_1") (pintype "passive"))
      (node (ref "U2") (pin "23") (pinfunction "IO15_23") (pintype "bidirectional"))
    )
    (net (code "19") (name "MISO") (class "Default")
      (node (ref "D12") (pin "2") (pinfunction "2_2") (pintype "passive"))
      (node (ref "J4") (pin "P7") (pinfunction "DAT0_P7") (pintype "bidirectional"))
      (node (ref "R8") (pin "1") (pinfunction "1_1") (pintype "passive"))
      (node (ref "TP6") (pin "TP") (pinfunction "TP_TP") (pintype "input"))
      (node (ref "U1") (pin "2") (pinfunction "DO(IO1)_2") (pintype "bidirectional"))
      (node (ref "U2") (pin "27") (pinfunction "IO2_27") (pintype "bidirectional"))
    )
    (net (code "20") (name "MOSI") (class "Default")
      (node (ref "D11") (pin "2") (pinfunction "2_2") (pintype "passive"))
      (node (ref "FH34SRJ-24S-0.5SH_99_") (pin "14") (pinfunction "14_14") (pintype "bidirectional"))
      (node (ref "J4") (pin "P3") (pinfunction "CMD_P3") (pintype "bidirectional"))
      (node (ref "R7") (pin "1") (pinfunction "1_1") (pintype "passive"))
      (node (ref "TP7") (pin "TP") (pinfunction "TP_TP") (pintype "input"))
      (node (ref "U1") (pin "5") (pinfunction "DI(IO0)_5") (pintype "bidirectional"))
      (node (ref "U2") (pin "7") (pinfunction "IO7_7") (pintype "bidirectional"))
    )
    (net (code "21") (name "Net-(CHG_LED-PadC)") (class "Default")
      (node (ref "CHG_LED") (pin "C") (pinfunction "C_C") (pintype "passive"))
      (node (ref "R1_BAT") (pin "1") (pinfunction "1_1") (pintype "passive"))
    )
    (net (code "22") (name "Net-(D2-CATHODE)") (class "Default")
      (node (ref "C1_BAT1") (pin "1") (pinfunction "1_1") (pintype "passive"))
      (node (ref "D2") (pin "1") (pinfunction "CATHODE_1") (pintype "bidirectional"))
      (node (ref "IC4") (pin "1") (pinfunction "VIN_1") (pintype "bidirectional"))
      (node (ref "IC4") (pin "3") (pinfunction "CE_3") (pintype "bidirectional"))
    )
    (net (code "23") (name "Net-(D3-A)") (class "Default")
      (node (ref "C4") (pin "1") (pinfunction "1_1") (pintype "passive"))
      (node (ref "D3") (pin "2") (pinfunction "A_2") (pintype "bidirectional"))
      (node (ref "D4") (pin "1") (pinfunction "K_1") (pintype "bidirectional"))
    )
    (net (code "24") (name "Net-(D7-CATHODE)") (class "Default")
      (node (ref "D7") (pin "1") (pinfunction "CATHODE_1") (pintype "bidirectional"))
      (node (ref "R_CAPACITOR") (pin "2") (pinfunction "2_2") (pintype "passive"))
    )
    (net (code "25") (name "Net-(EPD_C1-Pad2)") (class "Default")
      (node (ref "EPD_C1") (pin "2") (pinfunction "2_2") (pintype "passive"))
      (node (ref "FH34SRJ-24S-0.5SH_99_") (pin "4") (pinfunction "4_4") (pintype "bidirectional"))
    )
    (net (code "26") (name "Net-(EPD_C2-Pad2)") (class "Default")
      (node (ref "EPD_C2") (pin "2") (pinfunction "2_2") (pintype "passive"))
      (node (ref "FH34SRJ-24S-0.5SH_99_") (pin "5") (pinfunction "5_5") (pintype "bidirectional"))
    )
    (net (code "27") (name "Net-(EPD_C6-Pad2)") (class "Default")
      (node (ref "EPD_C6") (pin "2") (pinfunction "2_2") (pintype "passive"))
      (node (ref "FH34SRJ-24S-0.5SH_99_") (pin "18") (pinfunction "18_18") (pintype "bidirectional"))
    )
    (net (code "28") (name "Net-(EPD_C7-Pad2)") (class "Default")
      (node (ref "EPD_C7") (pin "2") (pinfunction "2_2") (pintype "passive"))
      (node (ref "FH34SRJ-24S-0.5SH_99_") (pin "19") (pinfunction "19_19") (pintype "bidirectional"))
    )
    (net (code "29") (name "Net-(EPD_C8-Pad2)") (class "Default")
      (node (ref "EPD_C8") (pin "2") (pinfunction "2_2") (pintype "passive"))
      (node (ref "FH34SRJ-24S-0.5SH_99_") (pin "20") (pinfunction "20_20") (pintype "bidirectional"))
    )
    (net (code "30") (name "Net-(EPD_C10-Pad2)") (class "Default")
      (node (ref "EPD_C10") (pin "2") (pinfunction "2_2") (pintype "passive"))
      (node (ref "FH34SRJ-24S-0.5SH_99_") (pin "22") (pinfunction "22_22") (pintype "bidirectional"))
    )
    (net (code "31") (name "Net-(EPD_C12-Pad2)") (class "Default")
      (node (ref "EPD_C12") (pin "2") (pinfunction "2_2") (pintype "passive"))
      (node (ref "FH34SRJ-24S-0.5SH_99_") (pin "24") (pinfunction "24_24") (pintype "bidirectional"))
    )
    (net (code "32") (name "Net-(IC1-CT)") (class "Default")
      (node (ref "C_DELAY") (pin "2") (pinfunction "2_2") (pintype "passive"))
      (node (ref "IC1") (pin "5") (pinfunction "CT_5") (pintype "bidirectional"))
    )
    (net (code "33") (name "Net-(J2-PadA5)") (class "Default")
      (node (ref "J2") (pin "A5") (pinfunction "A5_A5") (pintype "bidirectional"))
      (node (ref "R2_USB1") (pin "2") (pinfunction "2_2") (pintype "passive"))
    )
    (net (code "34") (name "Net-(J2-PadB5)") (class "Default")
      (node (ref "J2") (pin "B5") (pinfunction "B5_B5") (pintype "bidirectional"))
      (node (ref "R2_USB") (pin "1") (pinfunction "1_1") (pintype "passive"))
    )
    (net (code "35") (name "Net-(MCP73831-PROG)") (class "Default")
      (node (ref "MCP73831") (pin "5") (pinfunction "PROG_5") (pintype "input"))
      (node (ref "R2_BAT") (pin "2") (pinfunction "2_2") (pintype "passive"))
    )
    (net (code "36") (name "Net-(MCP73831-STAT)") (class "Default")
      (node (ref "MCP73831") (pin "1") (pinfunction "STAT_1") (pintype "output"))
      (node (ref "R1_BAT") (pin "2") (pinfunction "2_2") (pintype "passive"))
    )
    (net (code "37") (name "PREVGH") (class "Default")
      (node (ref "D5") (pin "1") (pinfunction "K_1") (pintype "bidirectional"))
      (node (ref "EPD_C9") (pin "2") (pinfunction "2_2") (pintype "passive"))
      (node (ref "FH34SRJ-24S-0.5SH_99_") (pin "21") (pinfunction "21_21") (pintype "bidirectional"))
    )
    (net (code "38") (name "PREVGL") (class "Default")
      (node (ref "D4") (pin "2") (pinfunction "A_2") (pintype "bidirectional"))
      (node (ref "EPD_C11") (pin "2") (pinfunction "2_2") (pintype "passive"))
      (node (ref "FH34SRJ-24S-0.5SH_99_") (pin "23") (pinfunction "23_23") (pintype "bidirectional"))
    )
    (net (code "39") (name "RESE") (class "Default")
      (node (ref "FH34SRJ-24S-0.5SH_99_") (pin "3") (pinfunction "3_3") (pintype "bidirectional"))
      (node (ref "Q3") (pin "2") (pinfunction "S_2") (pintype "bidirectional"))
      (node (ref "R3") (pin "2") (pinfunction "2_2") (pintype "passive"))
    )
    (net (code "40") (name "RESE'") (class "Default")
      (node (ref "R2") (pin "2") (pinfunction "2_2") (pintype "passive"))
      (node (ref "R3") (pin "1") (pinfunction "1_1") (pintype "passive"))
      (node (ref "SJ1") (pin "2") (pinfunction "2_2") (pintype "passive"))
    )
    (net (code "41") (name "RESET") (class "Default")
      (node (ref "C5") (pin "1") (pinfunction "1_1") (pintype "passive"))
      (node (ref "IC1") (pin "1") (pinfunction "VOUT_1") (pintype "bidirectional"))
      (node (ref "RESET_BUTTON") (pin "4") (pinfunction "4_4") (pintype "passive"))
      (node (ref "R_RESET") (pin "1") (pinfunction "1_1") (pintype "passive"))
      (node (ref "U2") (pin "3") (pinfunction "EN_3") (pintype "input"))
    )
    (net (code "42") (name "RTC_RST") (class "Default")
      (node (ref "U2") (pin "16") (pinfunction "IO18_16") (pintype "bidirectional"))
      (node (ref "U3") (pin "4") (pinfunction "~{RST}_4") (pintype "input"))
    )
    (net (code "43") (name "RX") (class "Default")
      (node (ref "TP2") (pin "TP") (pinfunction "TP_TP") (pintype "input"))
      (node (ref "U2") (pin "24") (pinfunction "RXD0/GPIO17_24") (pintype "bidirectional"))
    )
    (net (code "44") (name "SCK") (class "Default")
      (node (ref "D10") (pin "2") (pinfunction "2_2") (pintype "passive"))
      (node (ref "FH34SRJ-24S-0.5SH_99_") (pin "13") (pinfunction "13_13") (pintype "bidirectional"))
      (node (ref "J4") (pin "P5") (pinfunction "CLK_P5") (pintype "bidirectional"))
      (node (ref "R6") (pin "1") (pinfunction "1_1") (pintype "passive"))
      (node (ref "TP8") (pin "TP") (pinfunction "TP_TP") (pintype "input"))
      (node (ref "U1") (pin "6") (pinfunction "CLK_6") (pintype "input"))
      (node (ref "U2") (pin "6") (pinfunction "IO6_6") (pintype "bidirectional"))
    )
    (net (code "45") (name "SCL") (class "Default")
      (node (ref "J3") (pin "4") (pinfunction "4_4") (pintype "passive"))
      (node (ref "R2_PINH") (pin "1") (pinfunction "1_1") (pintype "passive"))
      (node (ref "SENSOR2") (pin "4") (pinfunction "SCK_4") (pintype "input"))
      (node (ref "U2") (pin "20") (pinfunction "IO22_20") (pintype "bidirectional"))
      (node (ref "U3") (pin "16") (pinfunction "SCL_16") (pintype "input"))
      (node (ref "U4") (pin "7") (pinfunction "SCL_7") (pintype "input"))
    )
    (net (code "46") (name "SDA") (class "Default")
      (node (ref "J3") (pin "3") (pinfunction "3_3") (pintype "passive"))
      (node (ref "R1_PINH") (pin "1") (pinfunction "1_1") (pintype "passive"))
      (node (ref "SENSOR2") (pin "3") (pinfunction "SDI_3") (pintype "bidirectional"))
      (node (ref "U2") (pin "19") (pinfunction "IO21_19") (pintype "bidirectional"))
      (node (ref "U3") (pin "15") (pinfunction "SDA_15") (pintype "bidirectional"))
      (node (ref "U4") (pin "8") (pinfunction "SDA_8") (pintype "bidirectional"))
    )
    (net (code "47") (name "SRC") (class "Default")
      (node (ref "C4") (pin "2") (pinfunction "2_2") (pintype "passive"))
      (node (ref "D5") (pin "2") (pinfunction "A_2") (pintype "bidirectional"))
      (node (ref "L1") (pin "1") (pinfunction "1_1") (pintype "passive"))
      (node (ref "Q3") (pin "3") (pinfunction "D_3") (pintype "bidirectional"))
    )
    (net (code "48") (name "SS_SD") (class "Default")
      (node (ref "D8") (pin "2") (pinfunction "2_2") (pintype "passive"))
      (node (ref "J4") (pin "P2") (pinfunction "CD/DAT3_P2") (pintype "bidirectional"))
      (node (ref "R10") (pin "1") (pinfunction "1_1") (pintype "passive"))
      (node (ref "U2") (pin "4") (pinfunction "IO4_4") (pintype "bidirectional"))
    )
    (net (code "49") (name "TX") (class "Default")
      (node (ref "TP1") (pin "TP") (pinfunction "TP_TP") (pintype "input"))
      (node (ref "U2") (pin "25") (pinfunction "TXD0/GPIO16_25") (pintype "bidirectional"))
    )
    (net (code "50") (name "USB_D+") (class "Default")
      (node (ref "D1") (pin "1") (pinfunction "I/O1_1_1") (pintype "bidirectional"))
      (node (ref "U2") (pin "14") (pinfunction "IO13_14") (pintype "bidirectional"))
    )
    (net (code "51") (name "USB_D-") (class "Default")
      (node (ref "D1") (pin "3") (pinfunction "I/O2_1_3") (pintype "bidirectional"))
      (node (ref "U2") (pin "13") (pinfunction "IO12_13") (pintype "bidirectional"))
    )
    (net (code "52") (name "VBAT") (class "Default")
      (node (ref "C2_BAT") (pin "1") (pinfunction "1_1") (pintype "passive"))
      (node (ref "MCP73831") (pin "3") (pinfunction "VBAT_3") (pintype "power_in"))
      (node (ref "Q1") (pin "3") (pinfunction "D_3") (pintype "bidirectional"))
      (node (ref "TP3") (pin "TP") (pinfunction "TP_TP") (pintype "input"))
      (node (ref "U4") (pin "2") (pinfunction "CELL_2") (pintype "power_in"))
      (node (ref "U4") (pin "3") (pinfunction "VDD_3") (pintype "power_in"))
    )
    (net (code "53") (name "VBUS") (class "Default")
      (node (ref "C1_BAT") (pin "1") (pinfunction "1_1") (pintype "passive"))
      (node (ref "C4_USB") (pin "1") (pinfunction "1_1") (pintype "passive"))
      (node (ref "C5_USB") (pin "1") (pinfunction "1_1") (pintype "passive"))
      (node (ref "CHG_LED") (pin "A") (pinfunction "A_A") (pintype "passive"))
      (node (ref "D1") (pin "5") (pinfunction "VBUS_5") (pintype "bidirectional"))
      (node (ref "D2") (pin "2") (pinfunction "ANODE_2") (pintype "bidirectional"))
      (node (ref "MCP73831") (pin "4") (pinfunction "VIN_4") (pintype "power_in"))
      (node (ref "PFMF.050.1") (pin "2") (pinfunction "2_2") (pintype "passive"))
      (node (ref "Q1") (pin "1") (pinfunction "G_1") (pintype "bidirectional"))
      (node (ref "R1_PWRUSB") (pin "2") (pinfunction "2_2") (pintype "passive"))
      (node (ref "TP14") (pin "TP") (pinfunction "TP_TP") (pintype "input"))
    )
    (net (code "54") (name "VRTC") (class "Default")
      (node (ref "C10_SUPERCAP") (pin "2") (pinfunction "2_2") (pintype "passive"))
      (node (ref "C8") (pin "1") (pinfunction "1_1") (pintype "passive"))
      (node (ref "R_CAPACITOR") (pin "1") (pinfunction "1_1") (pintype "passive"))
      (node (ref "U3") (pin "14") (pinfunction "VBAT_14") (pintype "power_in"))
    )
    (net (code "55") (name "VUSB") (class "Default")
      (node (ref "J2") (pin "A4") (pinfunction "A4_A4") (pintype "bidirectional"))
      (node (ref "J2") (pin "A9") (pinfunction "A9_A9") (pintype "bidirectional"))
      (node (ref "J2") (pin "B4") (pinfunction "B4_B4") (pintype "bidirectional"))
      (node (ref "J2") (pin "B9") (pinfunction "B9_B9") (pintype "bidirectional"))
      (node (ref "PFMF.050.1") (pin "1") (pinfunction "1_1") (pintype "passive"))
    )
    (net (code "56") (name "unconnected-(FH34SRJ-24S-0.5SH_99_-Pad1)") (class "Default")
      (node (ref "FH34SRJ-24S-0.5SH_99_") (pin "1") (pinfunction "1_1") (pintype "bidirectional"))
    )
    (net (code "57") (name "unconnected-(FH34SRJ-24S-0.5SH_99_-Pad6)") (class "Default")
      (node (ref "FH34SRJ-24S-0.5SH_99_") (pin "6") (pinfunction "6_6") (pintype "bidirectional"))
    )
    (net (code "58") (name "unconnected-(FH34SRJ-24S-0.5SH_99_-Pad7)") (class "Default")
      (node (ref "FH34SRJ-24S-0.5SH_99_") (pin "7") (pinfunction "7_7") (pintype "bidirectional"))
    )
    (net (code "59") (name "unconnected-(IC1-NC-Pad4)") (class "Default")
      (node (ref "IC1") (pin "4") (pinfunction "NC_4") (pintype "no_connect"))
    )
    (net (code "60") (name "unconnected-(IC4-NC-Pad4)") (class "Default")
      (node (ref "IC4") (pin "4") (pinfunction "NC_4") (pintype "no_connect"))
    )
    (net (code "61") (name "unconnected-(J2-PadA8)") (class "Default")
      (node (ref "J2") (pin "A8") (pinfunction "A8_A8") (pintype "bidirectional"))
    )
    (net (code "62") (name "unconnected-(J2-PadB8)") (class "Default")
      (node (ref "J2") (pin "B8") (pinfunction "B8_B8") (pintype "bidirectional"))
    )
    (net (code "63") (name "unconnected-(J4-DAT1-PadP8)") (class "Default")
      (node (ref "J4") (pin "P8") (pinfunction "DAT1_P8") (pintype "bidirectional"))
    )
    (net (code "64") (name "unconnected-(J4-DAT2-PadP1)") (class "Default")
      (node (ref "J4") (pin "P1") (pinfunction "DAT2_P1") (pintype "bidirectional"))
    )
    (net (code "65") (name "unconnected-(J4-DETECTION_1-PadS1)") (class "Default")
      (node (ref "J4") (pin "S1") (pinfunction "DETECTION_1_S1") (pintype "bidirectional"))
    )
    (net (code "66") (name "unconnected-(J4-DETECTION_2-PadS2)") (class "Default")
      (node (ref "J4") (pin "S2") (pinfunction "DETECTION_2_S2") (pintype "bidirectional"))
    )
    (net (code "67") (name "unconnected-(Q1-S-Pad2)") (class "Default")
      (node (ref "Q1") (pin "2") (pinfunction "S_2") (pintype "bidirectional"))
    )
    (net (code "68") (name "unconnected-(RESET_BUTTON-Pad1)") (class "Default")
      (node (ref "RESET_BUTTON") (pin "1") (pinfunction "1_1") (pintype "passive"))
    )
    (net (code "69") (name "unconnected-(RESET_BUTTON-Pad3)") (class "Default")
      (node (ref "RESET_BUTTON") (pin "3") (pinfunction "3_3") (pintype "passive"))
    )
    (net (code "70") (name "unconnected-(U2-NC-Pad22)") (class "Default")
      (node (ref "U2") (pin "22") (pinfunction "NC_22") (pintype "no_connect"))
    )
    (net (code "71") (name "unconnected-(U4-~{ALERT}-Pad5)") (class "Default")
      (node (ref "U4") (pin "5") (pinfunction "~{ALERT}_5") (pintype "output"))
    )
  )
)
